# Grove_Shield_for_Intel_Joule_v1_0.net
KiCad netlist of a schematic drawn in EAGLE
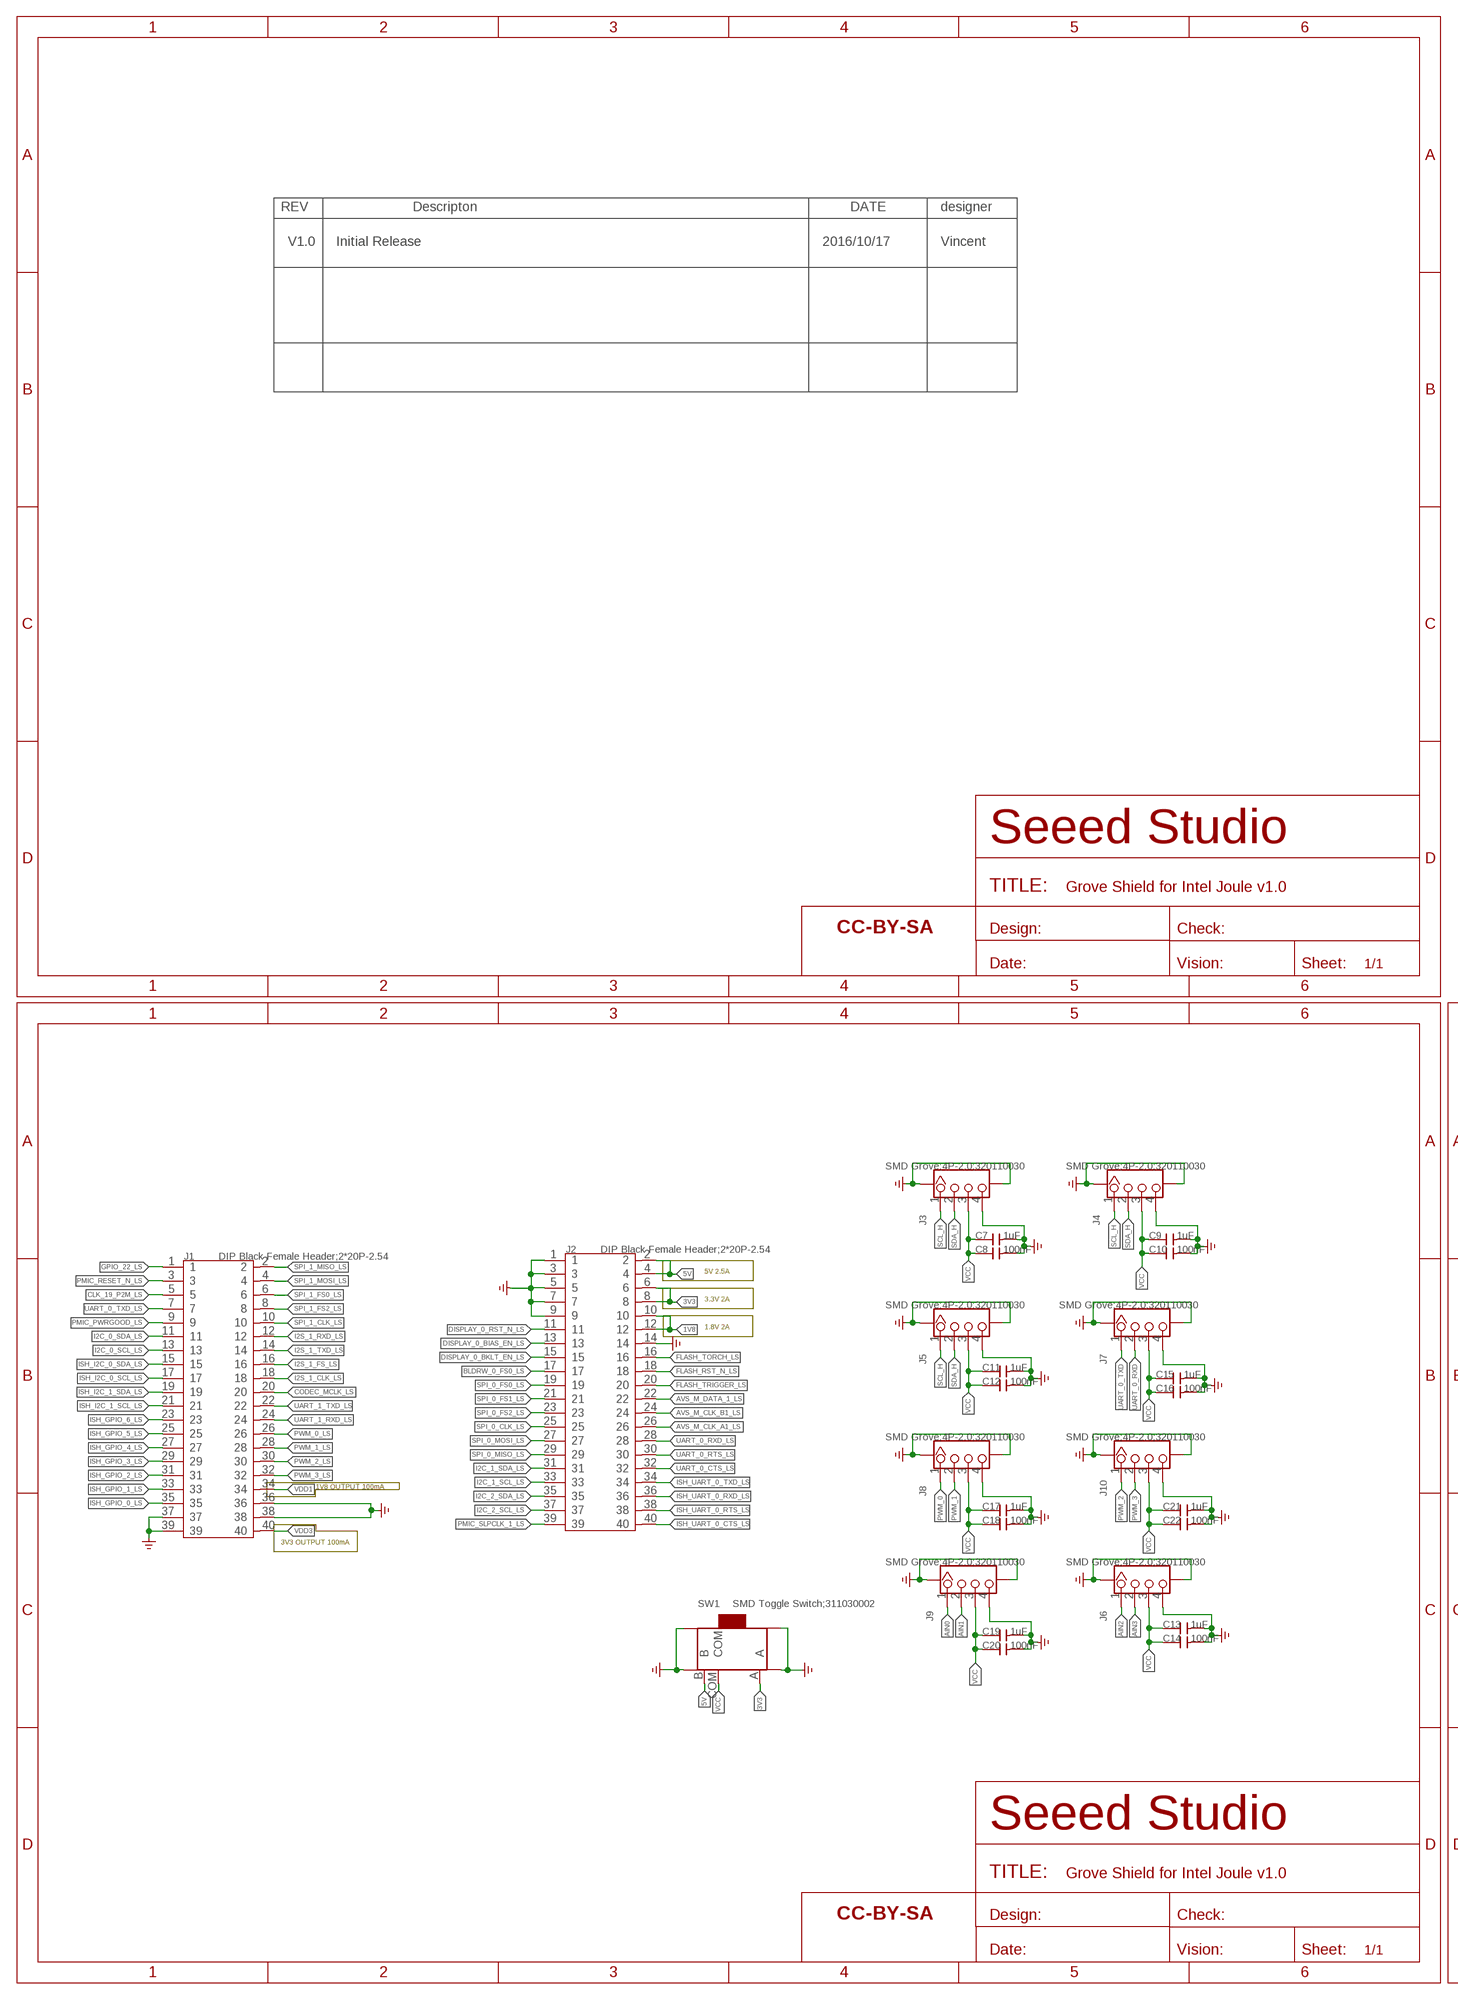
[diagram p0: schematic, sheet 1, part 1 of 2]
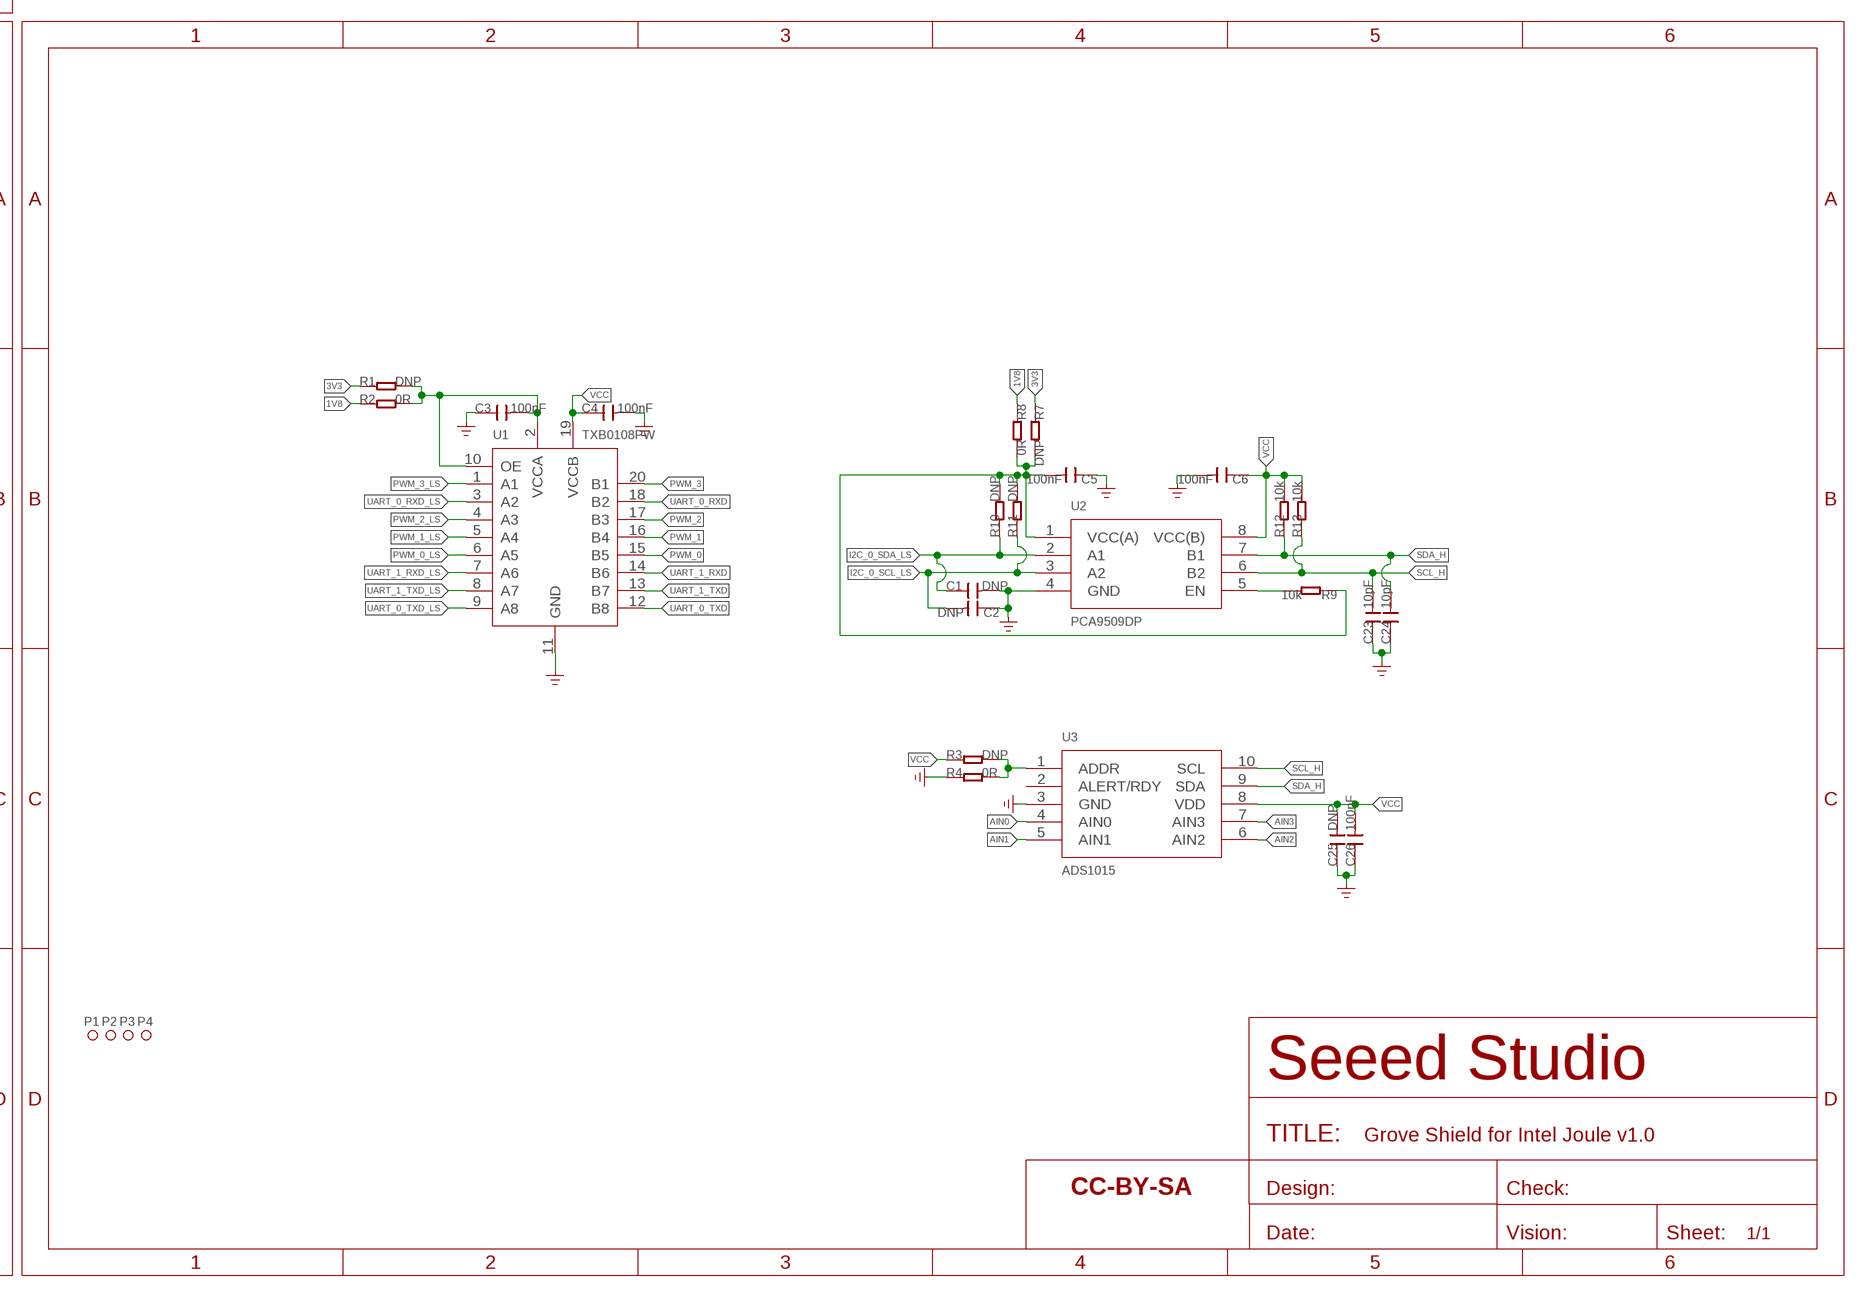
[diagram p1: schematic, sheet 1, part 2 of 2]

(export (version "E")
  (design (tool "Eeschema 10.0.6"))
  (components
    (comp (ref "C1")
      (value "DNP")
      (footprint "eagle-import:C0603")
      (libsource (lib "eagle-import") (part "CAP-0603"))
    )
    (comp (ref "C2")
      (value "DNP")
      (footprint "eagle-import:C0603")
      (libsource (lib "eagle-import") (part "CAP-0603"))
    )
    (comp (ref "C3")
      (value "100nF")
      (footprint "eagle-import:C0603")
      (libsource (lib "eagle-import") (part "CAP-0603"))
    )
    (comp (ref "C4")
      (value "100nF")
      (footprint "eagle-import:C0603")
      (libsource (lib "eagle-import") (part "CAP-0603"))
    )
    (comp (ref "C5")
      (value "100nF")
      (footprint "eagle-import:C0603")
      (libsource (lib "eagle-import") (part "CAP-0603"))
    )
    (comp (ref "C6")
      (value "100nF")
      (footprint "eagle-import:C0603")
      (libsource (lib "eagle-import") (part "CAP-0603"))
    )
    (comp (ref "C7")
      (value "1uF")
      (footprint "eagle-import:C0603")
      (libsource (lib "eagle-import") (part "CAP-0603"))
    )
    (comp (ref "C8")
      (value "100nF")
      (footprint "eagle-import:C0603")
      (libsource (lib "eagle-import") (part "CAP-0603"))
    )
    (comp (ref "C9")
      (value "1uF")
      (footprint "eagle-import:C0603")
      (libsource (lib "eagle-import") (part "CAP-0603"))
    )
    (comp (ref "C10")
      (value "100nF")
      (footprint "eagle-import:C0603")
      (libsource (lib "eagle-import") (part "CAP-0603"))
    )
    (comp (ref "C11")
      (value "1uF")
      (footprint "eagle-import:C0603")
      (libsource (lib "eagle-import") (part "CAP-0603"))
    )
    (comp (ref "C12")
      (value "100nF")
      (footprint "eagle-import:C0603")
      (libsource (lib "eagle-import") (part "CAP-0603"))
    )
    (comp (ref "C13")
      (value "1uF")
      (footprint "eagle-import:C0603")
      (libsource (lib "eagle-import") (part "CAP-0603"))
    )
    (comp (ref "C14")
      (value "100nF")
      (footprint "eagle-import:C0603")
      (libsource (lib "eagle-import") (part "CAP-0603"))
    )
    (comp (ref "C15")
      (value "1uF")
      (footprint "eagle-import:C0603")
      (libsource (lib "eagle-import") (part "CAP-0603"))
    )
    (comp (ref "C16")
      (value "100nF")
      (footprint "eagle-import:C0603")
      (libsource (lib "eagle-import") (part "CAP-0603"))
    )
    (comp (ref "C17")
      (value "1uF")
      (footprint "eagle-import:C0603")
      (libsource (lib "eagle-import") (part "CAP-0603"))
    )
    (comp (ref "C18")
      (value "100nF")
      (footprint "eagle-import:C0603")
      (libsource (lib "eagle-import") (part "CAP-0603"))
    )
    (comp (ref "C19")
      (value "1uF")
      (footprint "eagle-import:C0603")
      (libsource (lib "eagle-import") (part "CAP-0603"))
    )
    (comp (ref "C20")
      (value "100nF")
      (footprint "eagle-import:C0603")
      (libsource (lib "eagle-import") (part "CAP-0603"))
    )
    (comp (ref "C21")
      (value "1uF")
      (footprint "eagle-import:C0603")
      (libsource (lib "eagle-import") (part "CAP-0603"))
    )
    (comp (ref "C22")
      (value "100nF")
      (footprint "eagle-import:C0603")
      (libsource (lib "eagle-import") (part "CAP-0603"))
    )
    (comp (ref "C23")
      (value "10pF")
      (footprint "eagle-import:C0603")
      (libsource (lib "eagle-import") (part "CAP-0603"))
    )
    (comp (ref "C24")
      (value "10pF")
      (footprint "eagle-import:C0603")
      (libsource (lib "eagle-import") (part "CAP-0603"))
    )
    (comp (ref "C25")
      (value "DNP")
      (footprint "eagle-import:C0603")
      (libsource (lib "eagle-import") (part "CAP-0603"))
    )
    (comp (ref "C26")
      (value "100nF")
      (footprint "eagle-import:C0603")
      (libsource (lib "eagle-import") (part "CAP-0603"))
    )
    (comp (ref "FR1")
      (value "SEEEDSTUDIO-OPEN-SCH-FRAME")
      (footprint "eagle-import:SEEEDSTUDIO-PCB-FRAME")
      (libsource (lib "eagle-import") (part "SEEEDSTUDIO-OPEN-SCH-FRAME"))
    )
    (comp (ref "FR2")
      (value "SEEEDSTUDIO-OPEN-SCH-FRAME")
      (footprint "eagle-import:SEEEDSTUDIO-PCB-FRAME")
      (libsource (lib "eagle-import") (part "SEEEDSTUDIO-OPEN-SCH-FRAME"))
    )
    (comp (ref "FR3")
      (value "SEEEDSTUDIO-OPEN-SCH-FRAME")
      (footprint "eagle-import:SEEEDSTUDIO-PCB-FRAME")
      (libsource (lib "eagle-import") (part "SEEEDSTUDIO-OPEN-SCH-FRAME"))
    )
    (comp (ref "J1")
      (value "DIP Black Female Header;2*20P-2.54")
      (footprint "eagle-import:H2X20-2.54MM")
      (libsource (lib "eagle-import") (part "HEADER-2X20P-2.54"))
    )
    (comp (ref "J2")
      (value "DIP Black Female Header;2*20P-2.54")
      (footprint "eagle-import:H2X20-2.54MM")
      (libsource (lib "eagle-import") (part "HEADER-2X20P-2.54"))
    )
    (comp (ref "J3")
      (value "SMD Grove;4P-2.0;320110030")
      (footprint "eagle-import:HW4-SMD-2.0")
      (libsource (lib "eagle-import") (part "GROVE-CONNECTOR-SMD'DD'"))
    )
    (comp (ref "J4")
      (value "SMD Grove;4P-2.0;320110030")
      (footprint "eagle-import:HW4-SMD-2.0")
      (libsource (lib "eagle-import") (part "GROVE-CONNECTOR-SMD'DD'"))
    )
    (comp (ref "J5")
      (value "SMD Grove;4P-2.0;320110030")
      (footprint "eagle-import:HW4-SMD-2.0")
      (libsource (lib "eagle-import") (part "GROVE-CONNECTOR-SMD'DD'"))
    )
    (comp (ref "J6")
      (value "SMD Grove;4P-2.0;320110030")
      (footprint "eagle-import:HW4-SMD-2.0")
      (libsource (lib "eagle-import") (part "GROVE-CONNECTOR-SMD'DD'"))
    )
    (comp (ref "J7")
      (value "SMD Grove;4P-2.0;320110030")
      (footprint "eagle-import:HW4-SMD-2.0")
      (libsource (lib "eagle-import") (part "GROVE-CONNECTOR-SMD'DD'"))
    )
    (comp (ref "J8")
      (value "SMD Grove;4P-2.0;320110030")
      (footprint "eagle-import:HW4-SMD-2.0")
      (libsource (lib "eagle-import") (part "GROVE-CONNECTOR-SMD'DD'"))
    )
    (comp (ref "J9")
      (value "SMD Grove;4P-2.0;320110030")
      (footprint "eagle-import:HW4-SMD-2.0")
      (libsource (lib "eagle-import") (part "GROVE-CONNECTOR-SMD'DD'"))
    )
    (comp (ref "J10")
      (value "SMD Grove;4P-2.0;320110030")
      (footprint "eagle-import:HW4-SMD-2.0")
      (libsource (lib "eagle-import") (part "GROVE-CONNECTOR-SMD'DD'"))
    )
    (comp (ref "P1")
      (value "MARK-1.0'ANNULAR'")
      (footprint "eagle-import:ROUND-MARK-1.0")
      (fields (field (name "PARTNO") "DNP"))
      (libsource (lib "eagle-import") (part "MARK-1.0'ANNULAR'"))
    )
    (comp (ref "P2")
      (value "MARK-1.0'ANNULAR'")
      (footprint "eagle-import:ROUND-MARK-1.0")
      (fields (field (name "PARTNO") "DNP"))
      (libsource (lib "eagle-import") (part "MARK-1.0'ANNULAR'"))
    )
    (comp (ref "P3")
      (value "MARK-1.0'ANNULAR'")
      (footprint "eagle-import:ROUND-MARK-1.0")
      (fields (field (name "PARTNO") "DNP"))
      (libsource (lib "eagle-import") (part "MARK-1.0'ANNULAR'"))
    )
    (comp (ref "P4")
      (value "MARK-1.0'ANNULAR'")
      (footprint "eagle-import:ROUND-MARK-1.0")
      (fields (field (name "PARTNO") "DNP"))
      (libsource (lib "eagle-import") (part "MARK-1.0'ANNULAR'"))
    )
    (comp (ref "R1")
      (value "DNP")
      (footprint "eagle-import:R0603")
      (libsource (lib "eagle-import") (part "RES-0603"))
    )
    (comp (ref "R2")
      (value "0R")
      (footprint "eagle-import:R0603")
      (libsource (lib "eagle-import") (part "RES-0603"))
    )
    (comp (ref "R3")
      (value "DNP")
      (footprint "eagle-import:R0603")
      (libsource (lib "eagle-import") (part "RES-0603"))
    )
    (comp (ref "R4")
      (value "0R")
      (footprint "eagle-import:R0603")
      (libsource (lib "eagle-import") (part "RES-0603"))
    )
    (comp (ref "R7")
      (value "DNP")
      (footprint "eagle-import:R0603")
      (libsource (lib "eagle-import") (part "RES-0603"))
    )
    (comp (ref "R8")
      (value "0R")
      (footprint "eagle-import:R0603")
      (libsource (lib "eagle-import") (part "RES-0603"))
    )
    (comp (ref "R9")
      (value "10k")
      (footprint "eagle-import:R0603")
      (libsource (lib "eagle-import") (part "RES-0603"))
    )
    (comp (ref "R10")
      (value "DNP")
      (footprint "eagle-import:R0603")
      (libsource (lib "eagle-import") (part "RES-0603"))
    )
    (comp (ref "R11")
      (value "DNP")
      (footprint "eagle-import:R0603")
      (libsource (lib "eagle-import") (part "RES-0603"))
    )
    (comp (ref "R12")
      (value "10k")
      (footprint "eagle-import:R0603")
      (libsource (lib "eagle-import") (part "RES-0603"))
    )
    (comp (ref "R13")
      (value "10k")
      (footprint "eagle-import:R0603")
      (libsource (lib "eagle-import") (part "RES-0603"))
    )
    (comp (ref "SW1")
      (value "SMD Toggle Switch;311030002")
      (footprint "eagle-import:SW7-SMD-6.7X2.6X1.4MM-90D")
      (libsource (lib "eagle-import") (part "SWITCH-3+4P'90D'"))
    )
    (comp (ref "U1")
      (value "TXB0108PW")
      (footprint "eagle-import:TSSOP20-0.65-6.5X4.4MM")
      (libsource (lib "eagle-import") (part "LOGIC-TXS0108EPWR"))
    )
    (comp (ref "U2")
      (value "PCA9509DP")
      (footprint "eagle-import:TSSOP8-0.65-3X3MM")
      (libsource (lib "eagle-import") (part "LOGIC-PCA9509DP"))
    )
    (comp (ref "U3")
      (value "ADS1015")
      (footprint "eagle-import:SSOP10-0.5-3X3MM")
      (fields (field (name "MPN") "ADS1015IDGST-ADC-兼容1.8V-3.3V"))
      (libsource (lib "eagle-import") (part "CONVERTER-ADS1015IDGST-ADC"))
    )
  )
  (nets
    (net (code "1") (name "1V8") (class "Default")
      (node (ref "J2") (pin "10") (pinfunction "10_10") (pintype "bidirectional"))
      (node (ref "J2") (pin "12") (pinfunction "12_12") (pintype "bidirectional"))
      (node (ref "R2") (pin "1") (pinfunction "1_1") (pintype "passive"))
      (node (ref "R8") (pin "1") (pinfunction "1_1") (pintype "passive"))
    )
    (net (code "2") (name "3V3") (class "Default")
      (node (ref "J2") (pin "6") (pinfunction "6_6") (pintype "bidirectional"))
      (node (ref "J2") (pin "8") (pinfunction "8_8") (pintype "bidirectional"))
      (node (ref "R1") (pin "1") (pinfunction "1_1") (pintype "passive"))
      (node (ref "R7") (pin "1") (pinfunction "1_1") (pintype "passive"))
      (node (ref "SW1") (pin "A") (pinfunction "A_A") (pintype "bidirectional"))
    )
    (net (code "3") (name "5V") (class "Default")
      (node (ref "J2") (pin "2") (pinfunction "2_2") (pintype "bidirectional"))
      (node (ref "J2") (pin "4") (pinfunction "4_4") (pintype "bidirectional"))
      (node (ref "SW1") (pin "B") (pinfunction "B_B") (pintype "bidirectional"))
    )
    (net (code "4") (name "AIN0") (class "Default")
      (node (ref "J9") (pin "1") (pinfunction "1_1") (pintype "bidirectional"))
      (node (ref "U3") (pin "4") (pinfunction "AIN0_4") (pintype "bidirectional"))
    )
    (net (code "5") (name "AIN1") (class "Default")
      (node (ref "J9") (pin "2") (pinfunction "2_2") (pintype "bidirectional"))
      (node (ref "U3") (pin "5") (pinfunction "AIN1_5") (pintype "bidirectional"))
    )
    (net (code "6") (name "AIN2") (class "Default")
      (node (ref "J6") (pin "1") (pinfunction "1_1") (pintype "bidirectional"))
      (node (ref "U3") (pin "6") (pinfunction "AIN2_6") (pintype "bidirectional"))
    )
    (net (code "7") (name "AIN3") (class "Default")
      (node (ref "J6") (pin "2") (pinfunction "2_2") (pintype "bidirectional"))
      (node (ref "U3") (pin "7") (pinfunction "AIN3_7") (pintype "bidirectional"))
    )
    (net (code "8") (name "AVS_M_CLK_A1_LS") (class "Default")
      (node (ref "J2") (pin "26") (pinfunction "26_26") (pintype "bidirectional"))
    )
    (net (code "9") (name "AVS_M_CLK_B1_LS") (class "Default")
      (node (ref "J2") (pin "24") (pinfunction "24_24") (pintype "bidirectional"))
    )
    (net (code "10") (name "AVS_M_DATA_1_LS") (class "Default")
      (node (ref "J2") (pin "22") (pinfunction "22_22") (pintype "bidirectional"))
    )
    (net (code "11") (name "BLDRW_0_FS0_LS") (class "Default")
      (node (ref "J2") (pin "17") (pinfunction "17_17") (pintype "bidirectional"))
    )
    (net (code "12") (name "CLK_19_P2M_LS") (class "Default")
      (node (ref "J1") (pin "5") (pinfunction "5_5") (pintype "bidirectional"))
    )
    (net (code "13") (name "CODEC_MCLK_LS") (class "Default")
      (node (ref "J1") (pin "20") (pinfunction "20_20") (pintype "bidirectional"))
    )
    (net (code "14") (name "DISPLAY_0_BIAS_EN_LS") (class "Default")
      (node (ref "J2") (pin "13") (pinfunction "13_13") (pintype "bidirectional"))
    )
    (net (code "15") (name "DISPLAY_0_BKLT_EN_LS") (class "Default")
      (node (ref "J2") (pin "15") (pinfunction "15_15") (pintype "bidirectional"))
    )
    (net (code "16") (name "DISPLAY_0_RST_N_LS") (class "Default")
      (node (ref "J2") (pin "11") (pinfunction "11_11") (pintype "bidirectional"))
    )
    (net (code "17") (name "FLASH_RST_N_LS") (class "Default")
      (node (ref "J2") (pin "18") (pinfunction "18_18") (pintype "bidirectional"))
    )
    (net (code "18") (name "FLASH_TORCH_LS") (class "Default")
      (node (ref "J2") (pin "16") (pinfunction "16_16") (pintype "bidirectional"))
    )
    (net (code "19") (name "FLASH_TRIGGER_LS") (class "Default")
      (node (ref "J2") (pin "20") (pinfunction "20_20") (pintype "bidirectional"))
    )
    (net (code "20") (name "GND_POWER") (class "Default")
      (node (ref "C1") (pin "2") (pinfunction "2_2") (pintype "passive"))
      (node (ref "C10") (pin "2") (pinfunction "2_2") (pintype "passive"))
      (node (ref "C11") (pin "2") (pinfunction "2_2") (pintype "passive"))
      (node (ref "C12") (pin "2") (pinfunction "2_2") (pintype "passive"))
      (node (ref "C13") (pin "2") (pinfunction "2_2") (pintype "passive"))
      (node (ref "C14") (pin "2") (pinfunction "2_2") (pintype "passive"))
      (node (ref "C15") (pin "2") (pinfunction "2_2") (pintype "passive"))
      (node (ref "C16") (pin "2") (pinfunction "2_2") (pintype "passive"))
      (node (ref "C17") (pin "2") (pinfunction "2_2") (pintype "passive"))
      (node (ref "C18") (pin "2") (pinfunction "2_2") (pintype "passive"))
      (node (ref "C19") (pin "2") (pinfunction "2_2") (pintype "passive"))
      (node (ref "C2") (pin "1") (pinfunction "1_1") (pintype "passive"))
      (node (ref "C20") (pin "2") (pinfunction "2_2") (pintype "passive"))
      (node (ref "C21") (pin "2") (pinfunction "2_2") (pintype "passive"))
      (node (ref "C22") (pin "2") (pinfunction "2_2") (pintype "passive"))
      (node (ref "C23") (pin "1") (pinfunction "1_1") (pintype "passive"))
      (node (ref "C24") (pin "1") (pinfunction "1_1") (pintype "passive"))
      (node (ref "C25") (pin "1") (pinfunction "1_1") (pintype "passive"))
      (node (ref "C26") (pin "1") (pinfunction "1_1") (pintype "passive"))
      (node (ref "C3") (pin "1") (pinfunction "1_1") (pintype "passive"))
      (node (ref "C4") (pin "2") (pinfunction "2_2") (pintype "passive"))
      (node (ref "C5") (pin "1") (pinfunction "1_1") (pintype "passive"))
      (node (ref "C6") (pin "2") (pinfunction "2_2") (pintype "passive"))
      (node (ref "C7") (pin "2") (pinfunction "2_2") (pintype "passive"))
      (node (ref "C8") (pin "2") (pinfunction "2_2") (pintype "passive"))
      (node (ref "C9") (pin "2") (pinfunction "2_2") (pintype "passive"))
      (node (ref "J1") (pin "36") (pinfunction "36_36") (pintype "bidirectional"))
      (node (ref "J1") (pin "37") (pinfunction "37_37") (pintype "bidirectional"))
      (node (ref "J1") (pin "38") (pinfunction "38_38") (pintype "bidirectional"))
      (node (ref "J1") (pin "39") (pinfunction "39_39") (pintype "bidirectional"))
      (node (ref "J10") (pin "4") (pinfunction "4_4") (pintype "bidirectional"))
      (node (ref "J10") (pin "SS1") (pinfunction "SS1_SS1") (pintype "bidirectional"))
      (node (ref "J10") (pin "SS2") (pinfunction "SS2_SS2") (pintype "bidirectional"))
      (node (ref "J2") (pin "1") (pinfunction "1_1") (pintype "bidirectional"))
      (node (ref "J2") (pin "14") (pinfunction "14_14") (pintype "bidirectional"))
      (node (ref "J2") (pin "3") (pinfunction "3_3") (pintype "bidirectional"))
      (node (ref "J2") (pin "5") (pinfunction "5_5") (pintype "bidirectional"))
      (node (ref "J2") (pin "7") (pinfunction "7_7") (pintype "bidirectional"))
      (node (ref "J2") (pin "9") (pinfunction "9_9") (pintype "bidirectional"))
      (node (ref "J3") (pin "4") (pinfunction "4_4") (pintype "bidirectional"))
      (node (ref "J3") (pin "SS1") (pinfunction "SS1_SS1") (pintype "bidirectional"))
      (node (ref "J3") (pin "SS2") (pinfunction "SS2_SS2") (pintype "bidirectional"))
      (node (ref "J4") (pin "4") (pinfunction "4_4") (pintype "bidirectional"))
      (node (ref "J4") (pin "SS1") (pinfunction "SS1_SS1") (pintype "bidirectional"))
      (node (ref "J4") (pin "SS2") (pinfunction "SS2_SS2") (pintype "bidirectional"))
      (node (ref "J5") (pin "4") (pinfunction "4_4") (pintype "bidirectional"))
      (node (ref "J5") (pin "SS1") (pinfunction "SS1_SS1") (pintype "bidirectional"))
      (node (ref "J5") (pin "SS2") (pinfunction "SS2_SS2") (pintype "bidirectional"))
      (node (ref "J6") (pin "4") (pinfunction "4_4") (pintype "bidirectional"))
      (node (ref "J6") (pin "SS1") (pinfunction "SS1_SS1") (pintype "bidirectional"))
      (node (ref "J6") (pin "SS2") (pinfunction "SS2_SS2") (pintype "bidirectional"))
      (node (ref "J7") (pin "4") (pinfunction "4_4") (pintype "bidirectional"))
      (node (ref "J7") (pin "SS1") (pinfunction "SS1_SS1") (pintype "bidirectional"))
      (node (ref "J7") (pin "SS2") (pinfunction "SS2_SS2") (pintype "bidirectional"))
      (node (ref "J8") (pin "4") (pinfunction "4_4") (pintype "bidirectional"))
      (node (ref "J8") (pin "SS1") (pinfunction "SS1_SS1") (pintype "bidirectional"))
      (node (ref "J8") (pin "SS2") (pinfunction "SS2_SS2") (pintype "bidirectional"))
      (node (ref "J9") (pin "4") (pinfunction "4_4") (pintype "bidirectional"))
      (node (ref "J9") (pin "SS1") (pinfunction "SS1_SS1") (pintype "bidirectional"))
      (node (ref "J9") (pin "SS2") (pinfunction "SS2_SS2") (pintype "bidirectional"))
      (node (ref "R4") (pin "1") (pinfunction "1_1") (pintype "passive"))
      (node (ref "SW1") (pin "P1") (pinfunction "SS1_P1") (pintype "bidirectional"))
      (node (ref "SW1") (pin "P2") (pinfunction "SS2_P2") (pintype "bidirectional"))
      (node (ref "SW1") (pin "P3") (pinfunction "SS3_P3") (pintype "bidirectional"))
      (node (ref "SW1") (pin "P4") (pinfunction "SS4_P4") (pintype "bidirectional"))
      (node (ref "U1") (pin "11") (pinfunction "GND_11") (pintype "bidirectional"))
      (node (ref "U2") (pin "4") (pinfunction "GND_4") (pintype "open_collector"))
      (node (ref "U3") (pin "3") (pinfunction "GND_3") (pintype "bidirectional"))
    )
    (net (code "21") (name "GPIO_22_LS") (class "Default")
      (node (ref "J1") (pin "1") (pinfunction "1_1") (pintype "bidirectional"))
    )
    (net (code "22") (name "I2C_0_SCL_LS") (class "Default")
      (node (ref "C2") (pin "2") (pinfunction "2_2") (pintype "passive"))
      (node (ref "J1") (pin "13") (pinfunction "13_13") (pintype "bidirectional"))
      (node (ref "R11") (pin "1") (pinfunction "1_1") (pintype "passive"))
      (node (ref "U2") (pin "3") (pinfunction "A2_3") (pintype "open_collector"))
    )
    (net (code "23") (name "I2C_0_SDA_LS") (class "Default")
      (node (ref "C1") (pin "1") (pinfunction "1_1") (pintype "passive"))
      (node (ref "J1") (pin "11") (pinfunction "11_11") (pintype "bidirectional"))
      (node (ref "R10") (pin "1") (pinfunction "1_1") (pintype "passive"))
      (node (ref "U2") (pin "2") (pinfunction "A1_2") (pintype "open_collector"))
    )
    (net (code "24") (name "I2C_1_SCL_LS") (class "Default")
      (node (ref "J2") (pin "33") (pinfunction "33_33") (pintype "bidirectional"))
    )
    (net (code "25") (name "I2C_1_SDA_LS") (class "Default")
      (node (ref "J2") (pin "31") (pinfunction "31_31") (pintype "bidirectional"))
    )
    (net (code "26") (name "I2C_2_SCL_LS") (class "Default")
      (node (ref "J2") (pin "37") (pinfunction "37_37") (pintype "bidirectional"))
    )
    (net (code "27") (name "I2C_2_SDA_LS") (class "Default")
      (node (ref "J2") (pin "35") (pinfunction "35_35") (pintype "bidirectional"))
    )
    (net (code "28") (name "I2S_1_CLK_LS") (class "Default")
      (node (ref "J1") (pin "18") (pinfunction "18_18") (pintype "bidirectional"))
    )
    (net (code "29") (name "I2S_1_FS_LS") (class "Default")
      (node (ref "J1") (pin "16") (pinfunction "16_16") (pintype "bidirectional"))
    )
    (net (code "30") (name "I2S_1_RXD_LS") (class "Default")
      (node (ref "J1") (pin "12") (pinfunction "12_12") (pintype "bidirectional"))
    )
    (net (code "31") (name "I2S_1_TXD_LS") (class "Default")
      (node (ref "J1") (pin "14") (pinfunction "14_14") (pintype "bidirectional"))
    )
    (net (code "32") (name "ISH_GPIO_0_LS") (class "Default")
      (node (ref "J1") (pin "35") (pinfunction "35_35") (pintype "bidirectional"))
    )
    (net (code "33") (name "ISH_GPIO_1_LS") (class "Default")
      (node (ref "J1") (pin "33") (pinfunction "33_33") (pintype "bidirectional"))
    )
    (net (code "34") (name "ISH_GPIO_2_LS") (class "Default")
      (node (ref "J1") (pin "31") (pinfunction "31_31") (pintype "bidirectional"))
    )
    (net (code "35") (name "ISH_GPIO_3_LS") (class "Default")
      (node (ref "J1") (pin "29") (pinfunction "29_29") (pintype "bidirectional"))
    )
    (net (code "36") (name "ISH_GPIO_4_LS") (class "Default")
      (node (ref "J1") (pin "27") (pinfunction "27_27") (pintype "bidirectional"))
    )
    (net (code "37") (name "ISH_GPIO_5_LS") (class "Default")
      (node (ref "J1") (pin "25") (pinfunction "25_25") (pintype "bidirectional"))
    )
    (net (code "38") (name "ISH_GPIO_6_LS") (class "Default")
      (node (ref "J1") (pin "23") (pinfunction "23_23") (pintype "bidirectional"))
    )
    (net (code "39") (name "ISH_I2C_0_SCL_LS") (class "Default")
      (node (ref "J1") (pin "17") (pinfunction "17_17") (pintype "bidirectional"))
    )
    (net (code "40") (name "ISH_I2C_0_SDA_LS") (class "Default")
      (node (ref "J1") (pin "15") (pinfunction "15_15") (pintype "bidirectional"))
    )
    (net (code "41") (name "ISH_I2C_1_SCL_LS") (class "Default")
      (node (ref "J1") (pin "21") (pinfunction "21_21") (pintype "bidirectional"))
    )
    (net (code "42") (name "ISH_I2C_1_SDA_LS") (class "Default")
      (node (ref "J1") (pin "19") (pinfunction "19_19") (pintype "bidirectional"))
    )
    (net (code "43") (name "ISH_UART_0_CTS_LS") (class "Default")
      (node (ref "J2") (pin "40") (pinfunction "40_40") (pintype "bidirectional"))
    )
    (net (code "44") (name "ISH_UART_0_RTS_LS") (class "Default")
      (node (ref "J2") (pin "38") (pinfunction "38_38") (pintype "bidirectional"))
    )
    (net (code "45") (name "ISH_UART_0_RXD_LS") (class "Default")
      (node (ref "J2") (pin "36") (pinfunction "36_36") (pintype "bidirectional"))
    )
    (net (code "46") (name "ISH_UART_0_TXD_LS") (class "Default")
      (node (ref "J2") (pin "34") (pinfunction "34_34") (pintype "bidirectional"))
    )
    (net (code "47") (name "Net-(U1-OE)") (class "Default")
      (node (ref "C3") (pin "2") (pinfunction "2_2") (pintype "passive"))
      (node (ref "R1") (pin "2") (pinfunction "2_2") (pintype "passive"))
      (node (ref "R2") (pin "2") (pinfunction "2_2") (pintype "passive"))
      (node (ref "U1") (pin "10") (pinfunction "OE_10") (pintype "bidirectional"))
      (node (ref "U1") (pin "2") (pinfunction "VCCA_2") (pintype "bidirectional"))
    )
    (net (code "48") (name "Net-(U2-EN)") (class "Default")
      (node (ref "R9") (pin "2") (pinfunction "2_2") (pintype "passive"))
      (node (ref "U2") (pin "5") (pinfunction "EN_5") (pintype "open_collector"))
    )
    (net (code "49") (name "Net-(U2-VCC(A))") (class "Default")
      (node (ref "C5") (pin "2") (pinfunction "2_2") (pintype "passive"))
      (node (ref "R10") (pin "2") (pinfunction "2_2") (pintype "passive"))
      (node (ref "R11") (pin "2") (pinfunction "2_2") (pintype "passive"))
      (node (ref "R7") (pin "2") (pinfunction "2_2") (pintype "passive"))
      (node (ref "R8") (pin "2") (pinfunction "2_2") (pintype "passive"))
      (node (ref "R9") (pin "1") (pinfunction "1_1") (pintype "passive"))
      (node (ref "U2") (pin "1") (pinfunction "VCC(A)_1") (pintype "open_collector"))
    )
    (net (code "50") (name "Net-(U3-ADDR)") (class "Default")
      (node (ref "R3") (pin "2") (pinfunction "2_2") (pintype "passive"))
      (node (ref "R4") (pin "2") (pinfunction "2_2") (pintype "passive"))
      (node (ref "U3") (pin "1") (pinfunction "ADDR_1") (pintype "bidirectional"))
    )
    (net (code "51") (name "PMIC_PWRGOOD_LS") (class "Default")
      (node (ref "J1") (pin "9") (pinfunction "9_9") (pintype "bidirectional"))
    )
    (net (code "52") (name "PMIC_RESET_N_LS") (class "Default")
      (node (ref "J1") (pin "3") (pinfunction "3_3") (pintype "bidirectional"))
    )
    (net (code "53") (name "PMIC_SLPCLK_1_LS") (class "Default")
      (node (ref "J2") (pin "39") (pinfunction "39_39") (pintype "bidirectional"))
    )
    (net (code "54") (name "PWM_0") (class "Default")
      (node (ref "J8") (pin "1") (pinfunction "1_1") (pintype "bidirectional"))
      (node (ref "U1") (pin "15") (pinfunction "B5_15") (pintype "bidirectional"))
    )
    (net (code "55") (name "PWM_0_LS") (class "Default")
      (node (ref "J1") (pin "26") (pinfunction "26_26") (pintype "bidirectional"))
      (node (ref "U1") (pin "6") (pinfunction "A5_6") (pintype "bidirectional"))
    )
    (net (code "56") (name "PWM_1") (class "Default")
      (node (ref "J8") (pin "2") (pinfunction "2_2") (pintype "bidirectional"))
      (node (ref "U1") (pin "16") (pinfunction "B4_16") (pintype "bidirectional"))
    )
    (net (code "57") (name "PWM_1_LS") (class "Default")
      (node (ref "J1") (pin "28") (pinfunction "28_28") (pintype "bidirectional"))
      (node (ref "U1") (pin "5") (pinfunction "A4_5") (pintype "bidirectional"))
    )
    (net (code "58") (name "PWM_2") (class "Default")
      (node (ref "J10") (pin "1") (pinfunction "1_1") (pintype "bidirectional"))
      (node (ref "U1") (pin "17") (pinfunction "B3_17") (pintype "bidirectional"))
    )
    (net (code "59") (name "PWM_2_LS") (class "Default")
      (node (ref "J1") (pin "30") (pinfunction "30_30") (pintype "bidirectional"))
      (node (ref "U1") (pin "4") (pinfunction "A3_4") (pintype "bidirectional"))
    )
    (net (code "60") (name "PWM_3") (class "Default")
      (node (ref "J10") (pin "2") (pinfunction "2_2") (pintype "bidirectional"))
      (node (ref "U1") (pin "20") (pinfunction "B1_20") (pintype "bidirectional"))
    )
    (net (code "61") (name "PWM_3_LS") (class "Default")
      (node (ref "J1") (pin "32") (pinfunction "32_32") (pintype "bidirectional"))
      (node (ref "U1") (pin "1") (pinfunction "A1_1") (pintype "bidirectional"))
    )
    (net (code "62") (name "SCL_H") (class "Default")
      (node (ref "C23") (pin "2") (pinfunction "2_2") (pintype "passive"))
      (node (ref "J3") (pin "1") (pinfunction "1_1") (pintype "bidirectional"))
      (node (ref "J4") (pin "1") (pinfunction "1_1") (pintype "bidirectional"))
      (node (ref "J5") (pin "1") (pinfunction "1_1") (pintype "bidirectional"))
      (node (ref "R13") (pin "1") (pinfunction "1_1") (pintype "passive"))
      (node (ref "U2") (pin "6") (pinfunction "B2_6") (pintype "open_collector"))
      (node (ref "U3") (pin "10") (pinfunction "SCL_10") (pintype "bidirectional"))
    )
    (net (code "63") (name "SDA_H") (class "Default")
      (node (ref "C24") (pin "2") (pinfunction "2_2") (pintype "passive"))
      (node (ref "J3") (pin "2") (pinfunction "2_2") (pintype "bidirectional"))
      (node (ref "J4") (pin "2") (pinfunction "2_2") (pintype "bidirectional"))
      (node (ref "J5") (pin "2") (pinfunction "2_2") (pintype "bidirectional"))
      (node (ref "R12") (pin "1") (pinfunction "1_1") (pintype "passive"))
      (node (ref "U2") (pin "7") (pinfunction "B1_7") (pintype "open_collector"))
      (node (ref "U3") (pin "9") (pinfunction "SDA_9") (pintype "bidirectional"))
    )
    (net (code "64") (name "SPI_0_CLK_LS") (class "Default")
      (node (ref "J2") (pin "25") (pinfunction "25_25") (pintype "bidirectional"))
    )
    (net (code "65") (name "SPI_0_FS0_LS") (class "Default")
      (node (ref "J2") (pin "19") (pinfunction "19_19") (pintype "bidirectional"))
    )
    (net (code "66") (name "SPI_0_FS1_LS") (class "Default")
      (node (ref "J2") (pin "21") (pinfunction "21_21") (pintype "bidirectional"))
    )
    (net (code "67") (name "SPI_0_FS2_LS") (class "Default")
      (node (ref "J2") (pin "23") (pinfunction "23_23") (pintype "bidirectional"))
    )
    (net (code "68") (name "SPI_0_MISO_LS") (class "Default")
      (node (ref "J2") (pin "29") (pinfunction "29_29") (pintype "bidirectional"))
    )
    (net (code "69") (name "SPI_0_MOSI_LS") (class "Default")
      (node (ref "J2") (pin "27") (pinfunction "27_27") (pintype "bidirectional"))
    )
    (net (code "70") (name "SPI_1_CLK_LS") (class "Default")
      (node (ref "J1") (pin "10") (pinfunction "10_10") (pintype "bidirectional"))
    )
    (net (code "71") (name "SPI_1_FS0_LS") (class "Default")
      (node (ref "J1") (pin "6") (pinfunction "6_6") (pintype "bidirectional"))
    )
    (net (code "72") (name "SPI_1_FS2_LS") (class "Default")
      (node (ref "J1") (pin "8") (pinfunction "8_8") (pintype "bidirectional"))
    )
    (net (code "73") (name "SPI_1_MISO_LS") (class "Default")
      (node (ref "J1") (pin "2") (pinfunction "2_2") (pintype "bidirectional"))
    )
    (net (code "74") (name "SPI_1_MOSI_LS") (class "Default")
      (node (ref "J1") (pin "4") (pinfunction "4_4") (pintype "bidirectional"))
    )
    (net (code "75") (name "UART_0_CTS_LS") (class "Default")
      (node (ref "J2") (pin "32") (pinfunction "32_32") (pintype "bidirectional"))
    )
    (net (code "76") (name "UART_0_RTS_LS") (class "Default")
      (node (ref "J2") (pin "30") (pinfunction "30_30") (pintype "bidirectional"))
    )
    (net (code "77") (name "UART_0_RXD") (class "Default")
      (node (ref "J7") (pin "2") (pinfunction "2_2") (pintype "bidirectional"))
      (node (ref "U1") (pin "18") (pinfunction "B2_18") (pintype "bidirectional"))
    )
    (net (code "78") (name "UART_0_RXD_LS") (class "Default")
      (node (ref "J2") (pin "28") (pinfunction "28_28") (pintype "bidirectional"))
      (node (ref "U1") (pin "3") (pinfunction "A2_3") (pintype "bidirectional"))
    )
    (net (code "79") (name "UART_0_TXD") (class "Default")
      (node (ref "J7") (pin "1") (pinfunction "1_1") (pintype "bidirectional"))
      (node (ref "U1") (pin "12") (pinfunction "B8_12") (pintype "bidirectional"))
    )
    (net (code "80") (name "UART_0_TXD_LS") (class "Default")
      (node (ref "J1") (pin "7") (pinfunction "7_7") (pintype "bidirectional"))
      (node (ref "U1") (pin "9") (pinfunction "A8_9") (pintype "bidirectional"))
    )
    (net (code "81") (name "UART_1_RXD") (class "Default")
      (node (ref "U1") (pin "14") (pinfunction "B6_14") (pintype "bidirectional"))
    )
    (net (code "82") (name "UART_1_RXD_LS") (class "Default")
      (node (ref "J1") (pin "24") (pinfunction "24_24") (pintype "bidirectional"))
      (node (ref "U1") (pin "7") (pinfunction "A6_7") (pintype "bidirectional"))
    )
    (net (code "83") (name "UART_1_TXD") (class "Default")
      (node (ref "U1") (pin "13") (pinfunction "B7_13") (pintype "bidirectional"))
    )
    (net (code "84") (name "UART_1_TXD_LS") (class "Default")
      (node (ref "J1") (pin "22") (pinfunction "22_22") (pintype "bidirectional"))
      (node (ref "U1") (pin "8") (pinfunction "A7_8") (pintype "bidirectional"))
    )
    (net (code "85") (name "VCC") (class "Default")
      (node (ref "C10") (pin "1") (pinfunction "1_1") (pintype "passive"))
      (node (ref "C11") (pin "1") (pinfunction "1_1") (pintype "passive"))
      (node (ref "C12") (pin "1") (pinfunction "1_1") (pintype "passive"))
      (node (ref "C13") (pin "1") (pinfunction "1_1") (pintype "passive"))
      (node (ref "C14") (pin "1") (pinfunction "1_1") (pintype "passive"))
      (node (ref "C15") (pin "1") (pinfunction "1_1") (pintype "passive"))
      (node (ref "C16") (pin "1") (pinfunction "1_1") (pintype "passive"))
      (node (ref "C17") (pin "1") (pinfunction "1_1") (pintype "passive"))
      (node (ref "C18") (pin "1") (pinfunction "1_1") (pintype "passive"))
      (node (ref "C19") (pin "1") (pinfunction "1_1") (pintype "passive"))
      (node (ref "C20") (pin "1") (pinfunction "1_1") (pintype "passive"))
      (node (ref "C21") (pin "1") (pinfunction "1_1") (pintype "passive"))
      (node (ref "C22") (pin "1") (pinfunction "1_1") (pintype "passive"))
      (node (ref "C25") (pin "2") (pinfunction "2_2") (pintype "passive"))
      (node (ref "C26") (pin "2") (pinfunction "2_2") (pintype "passive"))
      (node (ref "C4") (pin "1") (pinfunction "1_1") (pintype "passive"))
      (node (ref "C6") (pin "1") (pinfunction "1_1") (pintype "passive"))
      (node (ref "C7") (pin "1") (pinfunction "1_1") (pintype "passive"))
      (node (ref "C8") (pin "1") (pinfunction "1_1") (pintype "passive"))
      (node (ref "C9") (pin "1") (pinfunction "1_1") (pintype "passive"))
      (node (ref "J10") (pin "3") (pinfunction "3_3") (pintype "bidirectional"))
      (node (ref "J3") (pin "3") (pinfunction "3_3") (pintype "bidirectional"))
      (node (ref "J4") (pin "3") (pinfunction "3_3") (pintype "bidirectional"))
      (node (ref "J5") (pin "3") (pinfunction "3_3") (pintype "bidirectional"))
      (node (ref "J6") (pin "3") (pinfunction "3_3") (pintype "bidirectional"))
      (node (ref "J7") (pin "3") (pinfunction "3_3") (pintype "bidirectional"))
      (node (ref "J8") (pin "3") (pinfunction "3_3") (pintype "bidirectional"))
      (node (ref "J9") (pin "3") (pinfunction "3_3") (pintype "bidirectional"))
      (node (ref "R12") (pin "2") (pinfunction "2_2") (pintype "passive"))
      (node (ref "R13") (pin "2") (pinfunction "2_2") (pintype "passive"))
      (node (ref "R3") (pin "1") (pinfunction "1_1") (pintype "passive"))
      (node (ref "SW1") (pin "COM") (pinfunction "COM_COM") (pintype "bidirectional"))
      (node (ref "U1") (pin "19") (pinfunction "VCCB_19") (pintype "bidirectional"))
      (node (ref "U2") (pin "8") (pinfunction "VCC(B)_8") (pintype "open_collector"))
      (node (ref "U3") (pin "8") (pinfunction "VDD_8") (pintype "bidirectional"))
    )
    (net (code "86") (name "VDD1") (class "Default")
      (node (ref "J1") (pin "34") (pinfunction "34_34") (pintype "bidirectional"))
    )
    (net (code "87") (name "VDD3") (class "Default")
      (node (ref "J1") (pin "40") (pinfunction "40_40") (pintype "bidirectional"))
    )
    (net (code "88") (name "unconnected-(U3-ALERT{slash}RDY-Pad2)") (class "Default")
      (node (ref "U3") (pin "2") (pinfunction "ALERT/RDY_2") (pintype "bidirectional"))
    )
  )
)
